# bugs.net
KiCad netlist of a schematic drawn in EAGLE
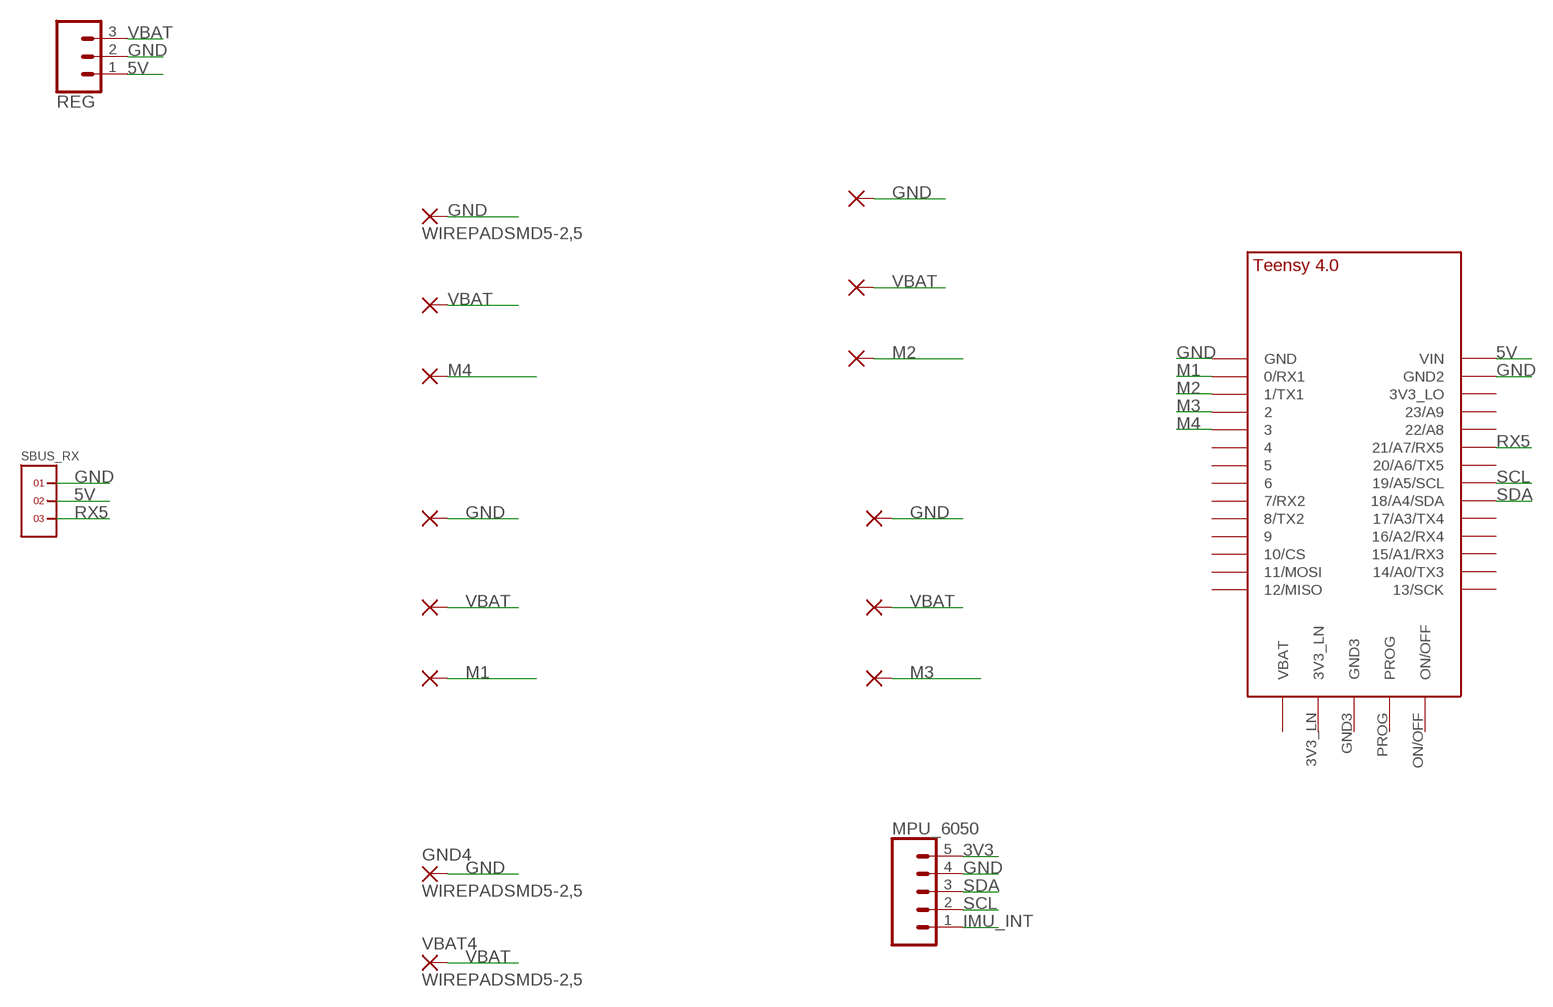
[diagram p0: schematic, sheet 1]

(export (version "E")
  (design (tool "Eeschema 10.0.6"))
  (components
    (comp (ref "GND")
      (value "WIREPADSMD5-2,5")
      (footprint "eagle-import:5-2,5")
      (libsource (lib "eagle-import") (part "WIREPADSMD5-2,5"))
    )
    (comp (ref "GND1")
      (value "WIREPADSMD5-2,5")
      (footprint "eagle-import:5-2,5")
      (libsource (lib "eagle-import") (part "WIREPADSMD5-2,5"))
    )
    (comp (ref "GND2")
      (value "WIREPADSMD5-2,5")
      (footprint "eagle-import:5-2,5")
      (libsource (lib "eagle-import") (part "WIREPADSMD5-2,5"))
    )
    (comp (ref "GND3")
      (value "WIREPADSMD5-2,5")
      (footprint "eagle-import:5-2,5")
      (libsource (lib "eagle-import") (part "WIREPADSMD5-2,5"))
    )
    (comp (ref "GND4")
      (value "WIREPADSMD5-2,5")
      (footprint "eagle-import:5-2,5")
      (libsource (lib "eagle-import") (part "WIREPADSMD5-2,5"))
    )
    (comp (ref "M1")
      (value "WIREPADSMD5-2,5")
      (footprint "eagle-import:5-2,5")
      (libsource (lib "eagle-import") (part "WIREPADSMD5-2,5"))
    )
    (comp (ref "M2")
      (value "WIREPADSMD5-2,5")
      (footprint "eagle-import:5-2,5")
      (libsource (lib "eagle-import") (part "WIREPADSMD5-2,5"))
    )
    (comp (ref "M3")
      (value "WIREPADSMD5-2,5")
      (footprint "eagle-import:5-2,5")
      (libsource (lib "eagle-import") (part "WIREPADSMD5-2,5"))
    )
    (comp (ref "M4")
      (value "WIREPADSMD5-2,5")
      (footprint "eagle-import:5-2,5")
      (libsource (lib "eagle-import") (part "WIREPADSMD5-2,5"))
    )
    (comp (ref "MPU_6050")
      (value "CONN_05NO_SILK")
      (footprint "eagle-import:1X05_NO_SILK")
      (libsource (lib "eagle-import") (part "CONN_05NO_SILK"))
    )
    (comp (ref "REG")
      (value "REG")
      (footprint "eagle-import:1X03_NO_SILK")
      (libsource (lib "eagle-import") (part "CONN_031X03_NO_SILK"))
    )
    (comp (ref "SBUS_RX")
      (value "1X3")
      (footprint "eagle-import:1X3")
      (libsource (lib "eagle-import") (part "1X3"))
    )
    (comp (ref "U$1")
      (value "TEENSY_4.0")
      (footprint "eagle-import:TEENSY_4.0")
      (libsource (lib "eagle-import") (part "TEENSY_4.0"))
    )
    (comp (ref "VBAT")
      (value "WIREPADSMD5-2,5")
      (footprint "eagle-import:5-2,5")
      (libsource (lib "eagle-import") (part "WIREPADSMD5-2,5"))
    )
    (comp (ref "VBAT1")
      (value "WIREPADSMD5-2,5")
      (footprint "eagle-import:5-2,5")
      (libsource (lib "eagle-import") (part "WIREPADSMD5-2,5"))
    )
    (comp (ref "VBAT2")
      (value "WIREPADSMD5-2,5")
      (footprint "eagle-import:5-2,5")
      (libsource (lib "eagle-import") (part "WIREPADSMD5-2,5"))
    )
    (comp (ref "VBAT3")
      (value "WIREPADSMD5-2,5")
      (footprint "eagle-import:5-2,5")
      (libsource (lib "eagle-import") (part "WIREPADSMD5-2,5"))
    )
    (comp (ref "VBAT4")
      (value "WIREPADSMD5-2,5")
      (footprint "eagle-import:5-2,5")
      (libsource (lib "eagle-import") (part "WIREPADSMD5-2,5"))
    )
  )
  (nets
    (net (code "1") (name "/3V3") (class "Default")
      (node (ref "MPU_6050") (pin "5") (pinfunction "5_5") (pintype "passive"))
    )
    (net (code "2") (name "/5V") (class "Default")
      (node (ref "REG") (pin "1") (pinfunction "1_1") (pintype "passive"))
      (node (ref "SBUS_RX") (pin "2") (pinfunction "2_2") (pintype "bidirectional"))
      (node (ref "U$1") (pin "VIN") (pinfunction "VIN_VIN") (pintype "bidirectional"))
    )
    (net (code "3") (name "/GND") (class "Default")
      (node (ref "GND") (pin "1") (pinfunction "P_1") (pintype "passive"))
      (node (ref "GND1") (pin "1") (pinfunction "P_1") (pintype "passive"))
      (node (ref "GND2") (pin "1") (pinfunction "P_1") (pintype "passive"))
      (node (ref "GND3") (pin "1") (pinfunction "P_1") (pintype "passive"))
      (node (ref "GND4") (pin "1") (pinfunction "P_1") (pintype "passive"))
      (node (ref "MPU_6050") (pin "4") (pinfunction "4_4") (pintype "passive"))
      (node (ref "REG") (pin "2") (pinfunction "2_2") (pintype "passive"))
      (node (ref "SBUS_RX") (pin "1") (pinfunction "1_1") (pintype "bidirectional"))
      (node (ref "U$1") (pin "GND") (pinfunction "GND_GND") (pintype "bidirectional"))
      (node (ref "U$1") (pin "GND2") (pinfunction "GND2_GND2") (pintype "bidirectional"))
    )
    (net (code "4") (name "/IMU_INT") (class "Default")
      (node (ref "MPU_6050") (pin "1") (pinfunction "1_1") (pintype "passive"))
    )
    (net (code "5") (name "/M1") (class "Default")
      (node (ref "M1") (pin "1") (pinfunction "P_1") (pintype "passive"))
      (node (ref "U$1") (pin "0/RX") (pinfunction "0/RX1_0/RX") (pintype "bidirectional"))
    )
    (net (code "6") (name "/M2") (class "Default")
      (node (ref "M2") (pin "1") (pinfunction "P_1") (pintype "passive"))
      (node (ref "U$1") (pin "1/TX") (pinfunction "1/TX1_1/TX") (pintype "bidirectional"))
    )
    (net (code "7") (name "/M3") (class "Default")
      (node (ref "M3") (pin "1") (pinfunction "P_1") (pintype "passive"))
      (node (ref "U$1") (pin "2") (pinfunction "2_2") (pintype "bidirectional"))
    )
    (net (code "8") (name "/M4") (class "Default")
      (node (ref "M4") (pin "1") (pinfunction "P_1") (pintype "passive"))
      (node (ref "U$1") (pin "3/CANTX") (pinfunction "3_3/CANTX") (pintype "bidirectional"))
    )
    (net (code "9") (name "/RX5") (class "Default")
      (node (ref "SBUS_RX") (pin "3") (pinfunction "3_3") (pintype "bidirectional"))
      (node (ref "U$1") (pin "21/A7") (pinfunction "21/A7/RX5_21/A7") (pintype "bidirectional"))
    )
    (net (code "10") (name "/SCL") (class "Default")
      (node (ref "MPU_6050") (pin "2") (pinfunction "2_2") (pintype "passive"))
      (node (ref "U$1") (pin "19/A5/SCL") (pinfunction "19/A5/SCL_19/A5/SCL") (pintype "bidirectional"))
    )
    (net (code "11") (name "/SDA") (class "Default")
      (node (ref "MPU_6050") (pin "3") (pinfunction "3_3") (pintype "passive"))
      (node (ref "U$1") (pin "18/A4/SDA") (pinfunction "18/A4/SDA_18/A4/SDA") (pintype "bidirectional"))
    )
    (net (code "12") (name "/VBAT") (class "Default")
      (node (ref "REG") (pin "3") (pinfunction "3_3") (pintype "passive"))
      (node (ref "VBAT") (pin "1") (pinfunction "P_1") (pintype "passive"))
      (node (ref "VBAT1") (pin "1") (pinfunction "P_1") (pintype "passive"))
      (node (ref "VBAT2") (pin "1") (pinfunction "P_1") (pintype "passive"))
      (node (ref "VBAT3") (pin "1") (pinfunction "P_1") (pintype "passive"))
      (node (ref "VBAT4") (pin "1") (pinfunction "P_1") (pintype "passive"))
    )
    (net (code "13") (name "unconnected-(U$1-4-Pad4{slash}CANRX)") (class "Default")
      (node (ref "U$1") (pin "4/CANRX") (pinfunction "4_4/CANRX") (pintype "bidirectional"))
    )
    (net (code "14") (name "unconnected-(U$1-7{slash}RX2-Pad7)") (class "Default")
      (node (ref "U$1") (pin "7") (pinfunction "7/RX2_7") (pintype "bidirectional"))
    )
    (net (code "15") (name "unconnected-(U$1-8{slash}TX2-Pad8)") (class "Default")
      (node (ref "U$1") (pin "8") (pinfunction "8/TX2_8") (pintype "bidirectional"))
    )
    (net (code "16") (name "unconnected-(U$1-9-Pad9{slash}CS)") (class "Default")
      (node (ref "U$1") (pin "9/CS") (pinfunction "9_9/CS") (pintype "bidirectional"))
    )
    (net (code "17") (name "unconnected-(U$1-14{slash}A0{slash}TX3-Pad14{slash}A0)") (class "Default")
      (node (ref "U$1") (pin "14/A0") (pinfunction "14/A0/TX3_14/A0") (pintype "bidirectional"))
    )
    (net (code "18") (name "unconnected-(U$1-15{slash}A1{slash}RX3-Pad15{slash}A1)") (class "Default")
      (node (ref "U$1") (pin "15/A1") (pinfunction "15/A1/RX3_15/A1") (pintype "bidirectional"))
    )
    (net (code "19") (name "unconnected-(U$1-16{slash}A2{slash}RX4-Pad16{slash}A2)") (class "Default")
      (node (ref "U$1") (pin "16/A2") (pinfunction "16/A2/RX4_16/A2") (pintype "bidirectional"))
    )
    (net (code "20") (name "unconnected-(U$1-17{slash}A3{slash}TX4-Pad17{slash}A3)") (class "Default")
      (node (ref "U$1") (pin "17/A3") (pinfunction "17/A3/TX4_17/A3") (pintype "bidirectional"))
    )
    (net (code "21") (name "unconnected-(U$1-20{slash}A6{slash}TX5-Pad20{slash}A6)") (class "Default")
      (node (ref "U$1") (pin "20/A6") (pinfunction "20/A6/TX5_20/A6") (pintype "bidirectional"))
    )
    (net (code "22") (name "unconnected-(U$1-Pad3V3_LN)") (class "Default")
      (node (ref "U$1") (pin "3V3_LN") (pinfunction "3V3_LN_3V3_LN") (pintype "bidirectional"))
    )
    (net (code "23") (name "unconnected-(U$1-Pad3V3_LO)") (class "Default")
      (node (ref "U$1") (pin "3V3_LO") (pinfunction "3V3_LO_3V3_LO") (pintype "bidirectional"))
    )
    (net (code "24") (name "unconnected-(U$1-Pad5)") (class "Default")
      (node (ref "U$1") (pin "5") (pinfunction "5_5") (pintype "bidirectional"))
    )
    (net (code "25") (name "unconnected-(U$1-Pad6)") (class "Default")
      (node (ref "U$1") (pin "6") (pinfunction "6_6") (pintype "bidirectional"))
    )
    (net (code "26") (name "unconnected-(U$1-Pad10{slash}CS)") (class "Default")
      (node (ref "U$1") (pin "10/CS") (pinfunction "10/CS_10/CS") (pintype "bidirectional"))
    )
    (net (code "27") (name "unconnected-(U$1-Pad11{slash}MOSI)") (class "Default")
      (node (ref "U$1") (pin "11/MOSI") (pinfunction "11/MOSI_11/MOSI") (pintype "bidirectional"))
    )
    (net (code "28") (name "unconnected-(U$1-Pad12{slash}MISO)") (class "Default")
      (node (ref "U$1") (pin "12/MISO") (pinfunction "12/MISO_12/MISO") (pintype "bidirectional"))
    )
    (net (code "29") (name "unconnected-(U$1-Pad13{slash}SCK)") (class "Default")
      (node (ref "U$1") (pin "13/SCK") (pinfunction "13/SCK_13/SCK") (pintype "bidirectional"))
    )
    (net (code "30") (name "unconnected-(U$1-Pad22{slash}A8)") (class "Default")
      (node (ref "U$1") (pin "22/A8") (pinfunction "22/A8_22/A8") (pintype "bidirectional"))
    )
    (net (code "31") (name "unconnected-(U$1-Pad23{slash}A9)") (class "Default")
      (node (ref "U$1") (pin "23/A9") (pinfunction "23/A9_23/A9") (pintype "bidirectional"))
    )
    (net (code "32") (name "unconnected-(U$1-PadGND3)") (class "Default")
      (node (ref "U$1") (pin "GND3") (pinfunction "GND3_GND3") (pintype "bidirectional"))
    )
    (net (code "33") (name "unconnected-(U$1-PadON{slash}OFF)") (class "Default")
      (node (ref "U$1") (pin "ON/OFF") (pinfunction "ON/OFF_ON/OFF") (pintype "bidirectional"))
    )
    (net (code "34") (name "unconnected-(U$1-PadPROG)") (class "Default")
      (node (ref "U$1") (pin "PROG") (pinfunction "PROG_PROG") (pintype "bidirectional"))
    )
    (net (code "35") (name "unconnected-(U$1-VBAT-PadVBAT\\)") (class "Default")
      (node (ref "U$1") (pin "VBAT\\") (pinfunction "VBAT_VBAT\\") (pintype "bidirectional"))
    )
  )
)
